# ECG_Patch.net
KiCad netlist of a schematic drawn in EAGLE
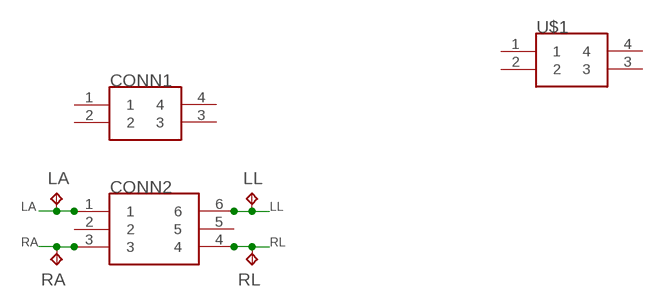
[diagram p0: schematic, sheet 1]

(export (version "E")
  (design (tool "Eeschema 10.0.6"))
  (components
    (comp (ref "CONN1")
      (value "M80-4V")
      (footprint "eagle-import:M80-4-V")
      (libsource (lib "eagle-import") (part "M80-4V"))
    )
    (comp (ref "CONN2")
      (value "M80-6V")
      (footprint "eagle-import:M80-6-V")
      (libsource (lib "eagle-import") (part "M80-6V"))
    )
    (comp (ref "LA")
      (value "TPTP20R")
      (footprint "eagle-import:TP20R")
      (libsource (lib "eagle-import") (part "TPTP20R"))
    )
    (comp (ref "LL")
      (value "TPTP20R")
      (footprint "eagle-import:TP20R")
      (libsource (lib "eagle-import") (part "TPTP20R"))
    )
    (comp (ref "RA")
      (value "TPTP20R")
      (footprint "eagle-import:TP20R")
      (libsource (lib "eagle-import") (part "TPTP20R"))
    )
    (comp (ref "RL")
      (value "TPTP20R")
      (footprint "eagle-import:TP20R")
      (libsource (lib "eagle-import") (part "TPTP20R"))
    )
    (comp (ref "U$1")
      (value "M80-4SMT")
      (footprint "eagle-import:M80-4_SMT")
      (libsource (lib "eagle-import") (part "M80-4SMT"))
    )
  )
  (nets
    (net (code "1") (name "/LA") (class "Default")
      (node (ref "CONN2") (pin "1") (pinfunction "1_1") (pintype "bidirectional"))
      (node (ref "LA") (pin "TP") (pinfunction "TP_TP") (pintype "input"))
    )
    (net (code "2") (name "/LL") (class "Default")
      (node (ref "CONN2") (pin "6") (pinfunction "6_6") (pintype "bidirectional"))
      (node (ref "LL") (pin "TP") (pinfunction "TP_TP") (pintype "input"))
    )
    (net (code "3") (name "/RA") (class "Default")
      (node (ref "CONN2") (pin "3") (pinfunction "3_3") (pintype "bidirectional"))
      (node (ref "RA") (pin "TP") (pinfunction "TP_TP") (pintype "input"))
    )
    (net (code "4") (name "/RL") (class "Default")
      (node (ref "CONN2") (pin "4") (pinfunction "4_4") (pintype "bidirectional"))
      (node (ref "RL") (pin "TP") (pinfunction "TP_TP") (pintype "input"))
    )
    (net (code "5") (name "unconnected-(CONN1-Pad1)") (class "Default")
      (node (ref "CONN1") (pin "1") (pinfunction "1_1") (pintype "bidirectional"))
    )
    (net (code "6") (name "unconnected-(CONN1-Pad2)") (class "Default")
      (node (ref "CONN1") (pin "2") (pinfunction "2_2") (pintype "bidirectional"))
    )
    (net (code "7") (name "unconnected-(CONN1-Pad3)") (class "Default")
      (node (ref "CONN1") (pin "3") (pinfunction "3_3") (pintype "bidirectional"))
    )
    (net (code "8") (name "unconnected-(CONN1-Pad4)") (class "Default")
      (node (ref "CONN1") (pin "4") (pinfunction "4_4") (pintype "bidirectional"))
    )
    (net (code "9") (name "unconnected-(CONN2-Pad2)") (class "Default")
      (node (ref "CONN2") (pin "2") (pinfunction "2_2") (pintype "bidirectional"))
    )
    (net (code "10") (name "unconnected-(CONN2-Pad5)") (class "Default")
      (node (ref "CONN2") (pin "5") (pinfunction "5_5") (pintype "bidirectional"))
    )
    (net (code "11") (name "unconnected-(U$1-Pad1)") (class "Default")
      (node (ref "U$1") (pin "1") (pinfunction "1_1") (pintype "bidirectional"))
    )
    (net (code "12") (name "unconnected-(U$1-Pad2)") (class "Default")
      (node (ref "U$1") (pin "2") (pinfunction "2_2") (pintype "bidirectional"))
    )
    (net (code "13") (name "unconnected-(U$1-Pad3)") (class "Default")
      (node (ref "U$1") (pin "3") (pinfunction "3_3") (pintype "bidirectional"))
    )
    (net (code "14") (name "unconnected-(U$1-Pad4)") (class "Default")
      (node (ref "U$1") (pin "4") (pinfunction "4_4") (pintype "bidirectional"))
    )
  )
)
